# MCUPOWER.net
KiCad netlist of a schematic drawn in Altium Designer
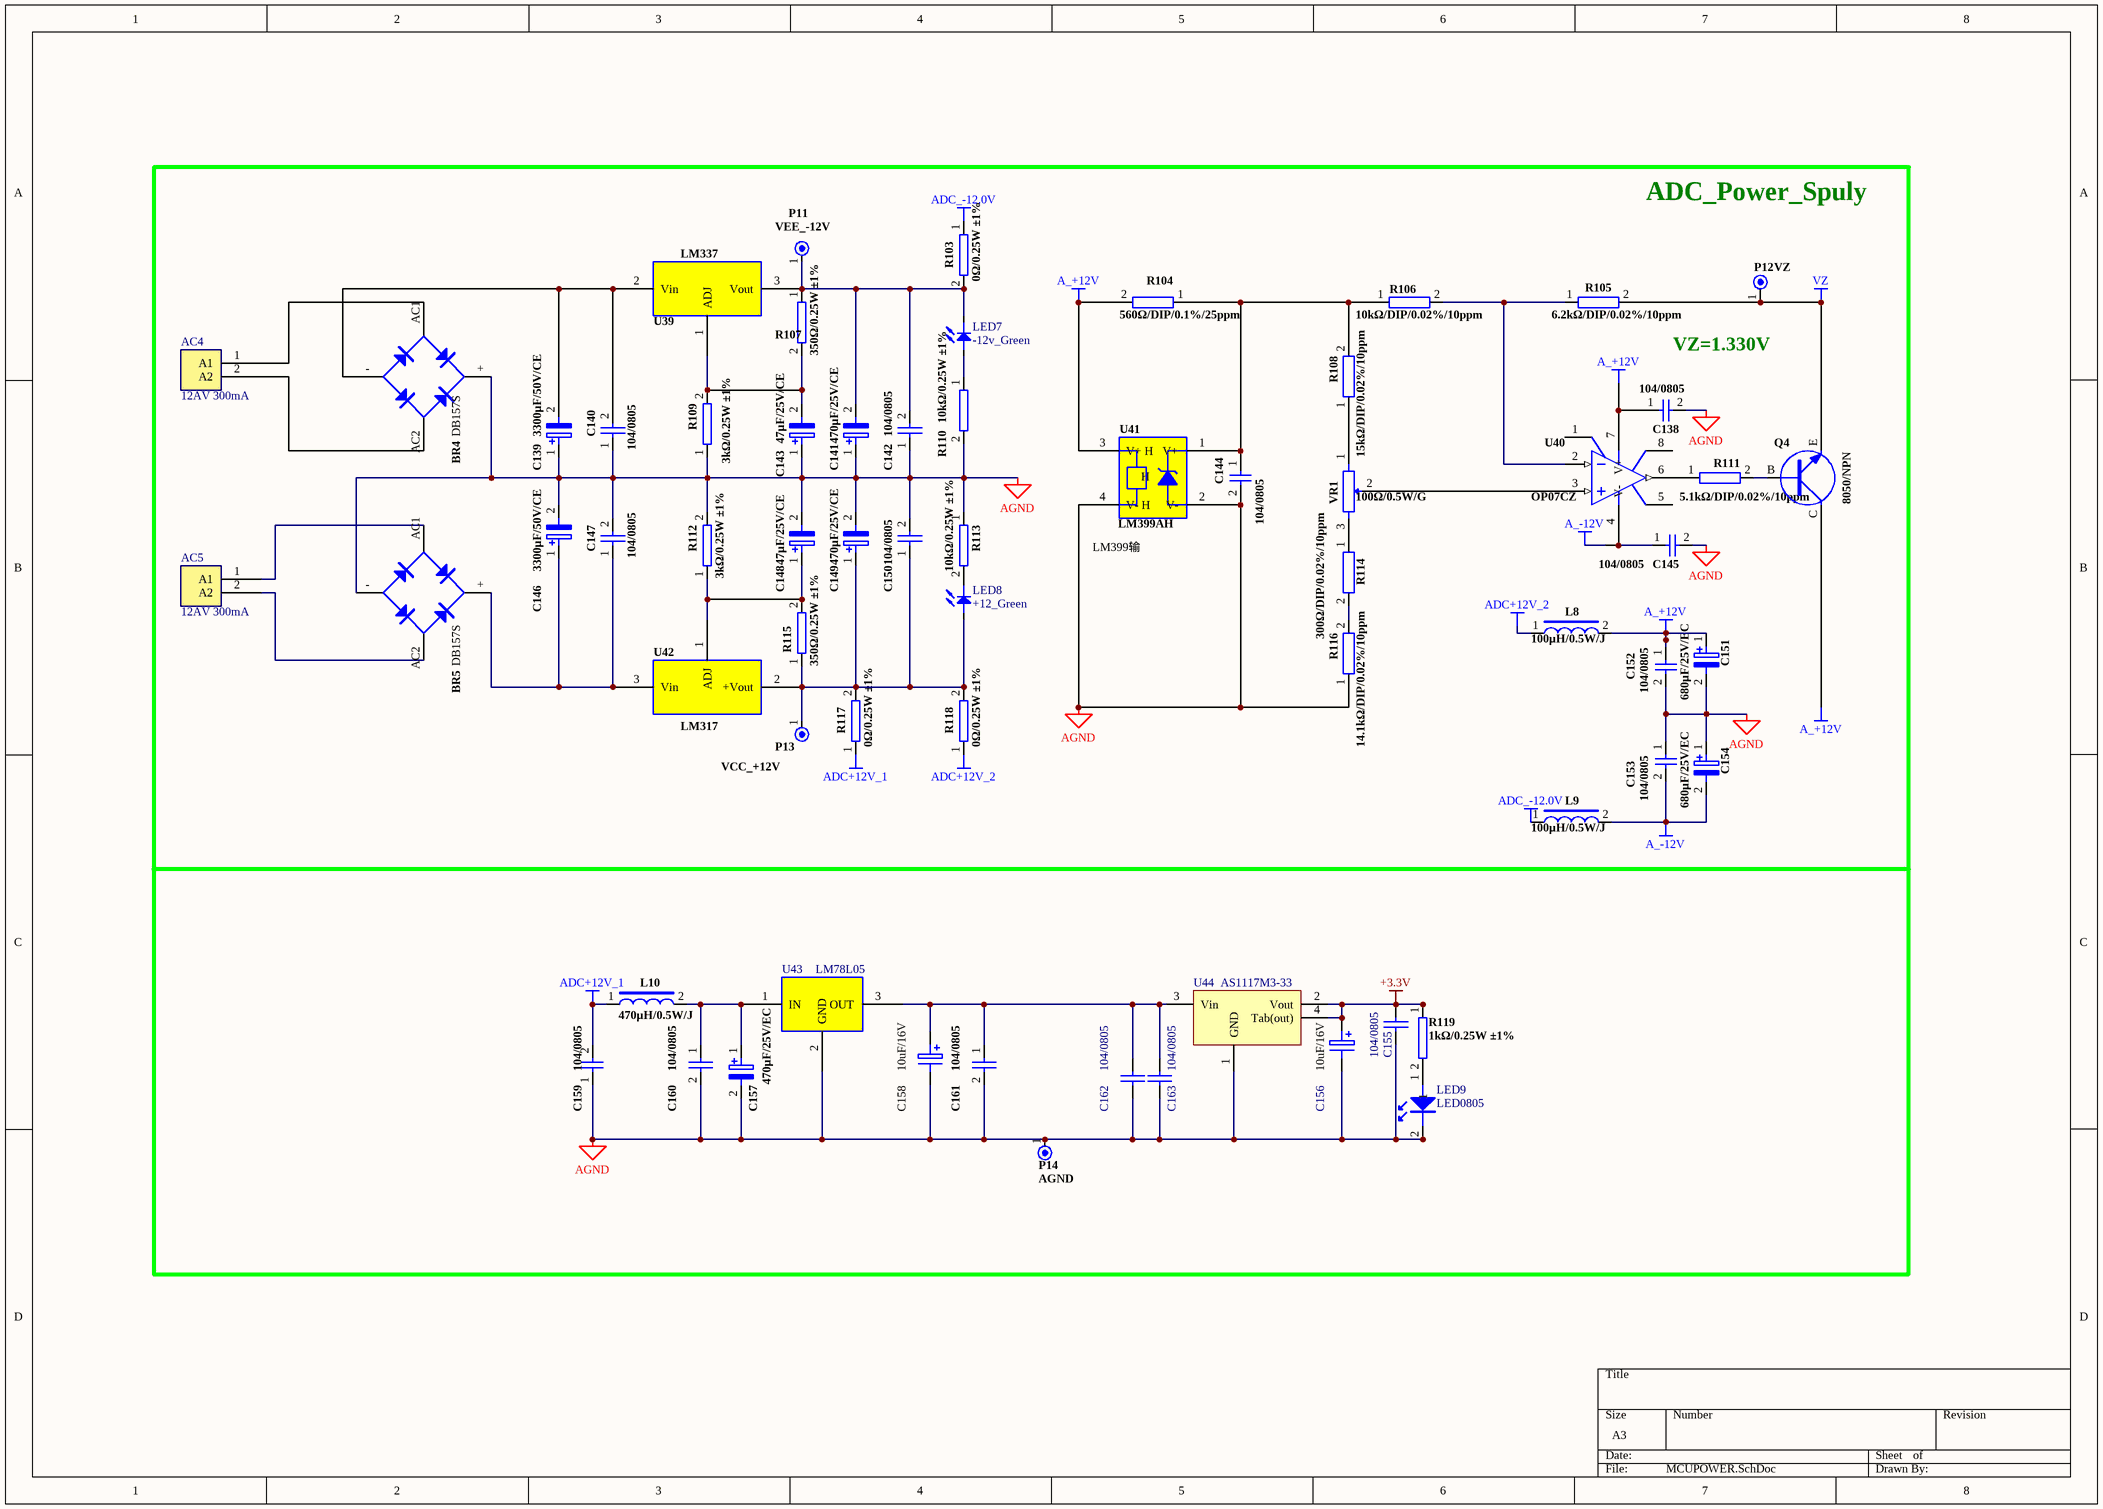
[diagram p0: MCUPOWER.SchDoc]

(export (version "E")
  (design (tool "Eeschema 10.0.6"))
  (components
    (comp (ref "AC4")
      (value "12AV 300mA")
      (footprint "HEADER2")
      (description "接线端子 AWG14-22 300VA 16A 5.0mm HEADER2")
      (libsource (lib "COOLCONTROL") (part "CON2"))
    )
    (comp (ref "AC5")
      (value "12AV 300mA")
      (footprint "HEADER2")
      (description "接线端子 AWG14-22 300VA 16A 5.0mm HEADER2")
      (libsource (lib "COOLCONTROL") (part "CON2"))
    )
    (comp (ref "BR4")
      (value "DB157S")
      (footprint "DB157S")
      (description "贴片整流桥 DB157S 50A/1000V")
      (libsource (lib "*") (part "NBRIDGE1"))
    )
    (comp (ref "BR5")
      (value "DB157S")
      (footprint "DB157S")
      (description "贴片整流桥 DB157S 50A/1000V")
      (libsource (lib "*") (part "NBRIDGE1"))
    )
    (comp (ref "C138")
      (value "104/0805")
      (footprint "C0805")
      (description "贴片电容 104/25V ±1% C0805")
      (libsource (lib "COOLCONTROL") (part "CAP"))
    )
    (comp (ref "C139")
      (value "3300μF/50V/CE")
      (footprint "RB.3/.6")
      (description "电解电容 3300μF/50V/CE ±10% RB.3/.6")
      (libsource (lib "*") (part "ELECTRO2"))
    )
    (comp (ref "C140")
      (value "104/0805")
      (footprint "C0805")
      (description "贴片电容 104/25V ±1% C0805")
      (libsource (lib "*") (part "CAP"))
    )
    (comp (ref "C141")
      (value "470μF/25V/CE")
      (footprint "RB.2/.4")
      (description "电解电容 470μF/25V/CE ±10% RB.2/.4")
      (libsource (lib "*") (part "ELECTRO2"))
    )
    (comp (ref "C142")
      (value "104/0805")
      (footprint "C0805")
      (description "贴片电容 104/25V ±1% C0805")
      (libsource (lib "*") (part "CAP"))
    )
    (comp (ref "C143")
      (value "47μF/25V/CE")
      (footprint "RB.1/.2")
      (description "电解电容 47μF/25V/CE ±10% RB.1/.2")
      (libsource (lib "*") (part "ELECTRO2"))
    )
    (comp (ref "C144")
      (value "104/0805")
      (footprint "C0805")
      (description "贴片电容 104/25V ±1% C0805")
      (libsource (lib "COOLCONTROL") (part "CAP"))
    )
    (comp (ref "C145")
      (value "104/0805")
      (footprint "C0805")
      (description "贴片电容 104/25V ±1% C0805")
      (libsource (lib "COOLCONTROL") (part "CAP"))
    )
    (comp (ref "C146")
      (value "3300μF/50V/CE")
      (footprint "RB.3/.6")
      (description "电解电容 3300μF/50V/CE ±10% RB.3/.6")
      (libsource (lib "*") (part "ELECTRO2"))
    )
    (comp (ref "C147")
      (value "104/0805")
      (footprint "C0805")
      (description "贴片电容 104/25V ±1% C0805")
      (libsource (lib "*") (part "CAP"))
    )
    (comp (ref "C148")
      (value "47μF/25V/CE")
      (footprint "RB.1/.2")
      (description "电解电容 47μF/25V/CE ±10% RB.1/.2")
      (libsource (lib "*") (part "ELECTRO2"))
    )
    (comp (ref "C149")
      (value "470μF/25V/CE")
      (footprint "RB.2/.4")
      (description "电解电容 470μF/25V/CE ±10% RB.2/.4")
      (libsource (lib "*") (part "ELECTRO2"))
    )
    (comp (ref "C150")
      (value "104/0805")
      (footprint "C0805")
      (description "贴片电容 104/25V ±1% C0805")
      (libsource (lib "*") (part "CAP"))
    )
    (comp (ref "C151")
      (value "680μF/25V/EC")
      (footprint "RB.2/.4")
      (description "电解电容 680μF/25V/EC ±10% RB.2/.4")
      (libsource (lib "COOLCONTROL") (part "ELECTRO2"))
    )
    (comp (ref "C152")
      (value "104/0805")
      (footprint "C0805")
      (description "贴片电容 104/25V ±1% C0805")
      (libsource (lib "COOLCONTROL") (part "CAP"))
    )
    (comp (ref "C153")
      (value "104/0805")
      (footprint "C0805")
      (description "贴片电容 104/25V ±1% C0805")
      (libsource (lib "COOLCONTROL") (part "CAP"))
    )
    (comp (ref "C154")
      (value "680μF/25V/EC")
      (footprint "RB.2/.4")
      (description "电解电容 680μF/25V/EC ±10% RB.2/.4")
      (libsource (lib "COOLCONTROL") (part "ELECTRO2"))
    )
    (comp (ref "C155")
      (value "104/0805")
      (footprint "C0805")
      (description "贴片电容 104/25V ±1% C0805")
      (libsource (lib "") (part "CAP_1"))
    )
    (comp (ref "C156")
      (value "10uF/16V")
      (footprint "C3216")
      (description "贴片钽电容 10uF/16V ±10% C3216")
      (libsource (lib "*") (part "ELECTRO1"))
    )
    (comp (ref "C157")
      (value "470μF/25V/EC")
      (footprint "RB.2/.4")
      (description "电解电容 470μF/25V/EC ±10% RB.2/.4")
      (libsource (lib "COOLCONTROL") (part "ELECTRO2"))
    )
    (comp (ref "C158")
      (value "10uF/16V")
      (footprint "C3216")
      (description "贴片钽电容 10uF/16V ±1% C3216")
      (libsource (lib "*") (part "ELECTRO1"))
    )
    (comp (ref "C159")
      (value "104/0805")
      (footprint "C0805")
      (description "贴片电容 104/25V ±1% C0805")
      (libsource (lib "") (part "CAP_2"))
    )
    (comp (ref "C160")
      (value "104/0805")
      (footprint "C0805")
      (description "贴片电容 104/25V ±1% C0805")
      (libsource (lib "*") (part "CAP"))
    )
    (comp (ref "C161")
      (value "104/0805")
      (footprint "C0805")
      (description "贴片电容 104/25V ±1% C0805")
      (libsource (lib "*") (part "CAP"))
    )
    (comp (ref "C162")
      (value "104/0805")
      (footprint "C0805")
      (description "贴片电容 104/25V ±1% C0805")
      (libsource (lib "") (part "CAP_1"))
    )
    (comp (ref "C163")
      (value "104/0805")
      (footprint "C0805")
      (description "贴片电容 104/25V ±1% C0805")
      (libsource (lib "") (part "CAP_1"))
    )
    (comp (ref "L8")
      (value "100μH/0.5W/J")
      (footprint "AXIAL0.4")
      (description "直插电感 100μH/0.5W ±5% AXIAL0.4")
      (libsource (lib "COOLCONTROL") (part "INDUCTOR2"))
    )
    (comp (ref "L9")
      (value "100μH/0.5W/J")
      (footprint "AXIAL0.4")
      (description "直插电感 100μH/0.5W ±5% AXIAL0.4")
      (libsource (lib "COOLCONTROL") (part "INDUCTOR2"))
    )
    (comp (ref "L10")
      (value "470μH/0.5W/J")
      (footprint "COOLCONTROL:AXIAL0.4")
      (description "直插电感 470μH/0.5W ±5% AXIAL0.4")
      (libsource (lib "COOLCONTROL") (part "INDUCTOR2"))
    )
    (comp (ref "LED7")
      (value "-12v_Green")
      (footprint "LED_0805")
      (description "贴片LED灯 绿色 2.0V 20mA LED_0805")
      (libsource (lib "COOLCONTROL") (part "B_LED"))
    )
    (comp (ref "LED8")
      (value "+12_Green")
      (footprint "LED_0805")
      (description "贴片LED灯 绿色 2.0V 20mA LED_0805")
      (libsource (lib "MasterBoard_Prj") (part "B_LED"))
    )
    (comp (ref "LED9")
      (value "LED0805")
      (footprint "LED_0805")
      (description "贴片LED灯 蓝色 2.0V 20mA LED_0805")
      (libsource (lib "COOLCONTROL") (part "LED0805"))
    )
    (comp (ref "P11")
      (value "VEE_-12V")
      (footprint "TESTSMD")
      (description "测试点")
      (libsource (lib "*") (part "CON1"))
    )
    (comp (ref "P12")
      (value "VZ")
      (footprint "COOLCONTROL:TESTSMD")
      (description "测试点")
      (libsource (lib "COOLCONTROL") (part "CON1"))
    )
    (comp (ref "P13")
      (value "VCC_+12V")
      (footprint "TESTSMD")
      (description "测试点")
      (libsource (lib "*") (part "CON1"))
    )
    (comp (ref "P14")
      (value "AGND")
      (footprint "TESTSMD")
      (description "测试点")
      (libsource (lib "*") (part "CON1"))
    )
    (comp (ref "Q4")
      (value "8050/NPN")
      (footprint "TO92A")
      (description "三极管 8050/NPN TO92A")
      (libsource (lib "COOLCONTROL") (part "NPN"))
    )
    (comp (ref "R103")
      (value "0Ω/0.25W ±1%")
      (footprint "R0805")
      (description "贴片电阻 0Ω 0.25W ±1% R0805")
      (libsource (lib "*") (part "RES2"))
    )
    (comp (ref "R104")
      (value "560Ω/DIP/0.1%/25ppm")
      (footprint "AXIAL-0.6-R")
      (description "高精度电阻 560Ω DIP 1W ±0.1% 25ppm AXIAL-0.6-R")
      (libsource (lib "COOLCONTROL") (part "RES2"))
    )
    (comp (ref "R105")
      (value "6.2kΩ/DIP/0.02%/10ppm")
      (footprint "AXIAL-0.6-R")
      (description "高精度电阻 6.2kΩ DIP 1W ±0.02% 10ppm AXIAL-0.6-R")
      (libsource (lib "") (part "RES3_1"))
    )
    (comp (ref "R106")
      (value "10kΩ/DIP/0.02%/10ppm")
      (footprint "AXIAL-0.6-R")
      (description "高精度电阻 10kΩ DIP 1W ±0.02% 10ppm AXIAL-0.6-R")
      (libsource (lib "") (part "RES3_1"))
    )
    (comp (ref "R107")
      (value "350Ω/0.25W ±1%")
      (footprint "R0805")
      (description "贴片电阻 350Ω 0.25W ±1% R0805")
      (libsource (lib "*") (part "RES2"))
    )
    (comp (ref "R108")
      (value "15kΩ/DIP/0.02%/10ppm")
      (footprint "AXIAL-0.6-R")
      (description "高精度电阻 15kΩ DIP 1W ±0.02% 10ppm AXIAL-0.6-R")
      (libsource (lib "COOLCONTROL") (part "RES3"))
    )
    (comp (ref "R109")
      (value "3kΩ/0.25W ±1%")
      (footprint "R0805")
      (description "贴片电阻 3kΩ 0.25W ±1% R0805")
      (libsource (lib "*") (part "RES2"))
    )
    (comp (ref "R110")
      (value "10kΩ/0.25W ±1%")
      (footprint "R0805")
      (description "贴片电阻 10kΩ 0.25W ±1% R0805")
      (libsource (lib "*") (part "RES2"))
    )
    (comp (ref "R111")
      (value "5.1kΩ/DIP/0.02%/10ppm")
      (footprint "AXIAL-0.6-R")
      (description "高精度电阻 5.1kΩ DIP 1W ±0.02% 10ppm AXIAL-0.6-R")
      (libsource (lib "") (part "RES2_1"))
    )
    (comp (ref "R112")
      (value "3kΩ/0.25W ±1%")
      (footprint "R0805")
      (description "贴片电阻 3kΩ 0.25W ±1% R0805")
      (libsource (lib "*") (part "RES2"))
    )
    (comp (ref "R113")
      (value "10kΩ/0.25W ±1%")
      (footprint "R0805")
      (description "贴片电阻 10kΩ 0.25W ±1% R0805")
      (libsource (lib "*") (part "RES2"))
    )
    (comp (ref "R114")
      (value "300Ω/DIP/0.02%/10ppm")
      (footprint "AXIAL-0.6-R")
      (description "高精度电阻 300Ω DIP 1W ±0.02% 10ppm AXIAL-0.6-R")
      (libsource (lib "") (part "RES2_2"))
    )
    (comp (ref "R115")
      (value "350Ω/0.25W ±1%")
      (footprint "R0805")
      (description "贴片电阻 350Ω 0.25W ±1% R0805")
      (libsource (lib "*") (part "RES2"))
    )
    (comp (ref "R116")
      (value "14.1kΩ/DIP/0.02%/10ppm")
      (footprint "AXIAL-0.6-R")
      (description "高精度电阻 14.1kΩ DIP 1W ±0.02% 10ppm AXIAL-0.6-R")
      (libsource (lib "COOLCONTROL") (part "RES3"))
    )
    (comp (ref "R117")
      (value "0Ω/0.25W ±1%")
      (footprint "R0805")
      (description "贴片电阻 0Ω 0.25W ±1% R0805")
      (libsource (lib "*") (part "RES2"))
    )
    (comp (ref "R118")
      (value "0Ω/0.25W ±1%")
      (footprint "R0805")
      (description "贴片电阻 0Ω 0.25W ±1% R0805")
      (libsource (lib "*") (part "RES2"))
    )
    (comp (ref "R119")
      (value "1kΩ/0.25W ±1%")
      (footprint "R0805")
      (description "贴片电阻 1kΩ 0.25W ±1% R0805")
      (libsource (lib "*") (part "RES2"))
    )
    (comp (ref "U39")
      (value "LM337")
      (footprint "TO220H")
      (description "线性可调稳压IC LM337 TO220H")
      (libsource (lib "*") (part "LM337"))
    )
    (comp (ref "U40")
      (value "OP07CZ")
      (footprint "SO-8")
      (description "运算放大器 OP07CZ SO-8")
      (libsource (lib "COOLCONTROL") (part "OP07CZ"))
    )
    (comp (ref "U41")
      (value "LM399AH")
      (footprint "LM399")
      (description "高精度电压比较器 LM399AH TO46-4")
      (libsource (lib "COOLCONTROL") (part "LM399AH"))
    )
    (comp (ref "U42")
      (value "LM317")
      (footprint "TO220H")
      (description "线性可调稳压IC LM317 TO220H")
      (libsource (lib "*") (part "LM317"))
    )
    (comp (ref "U43")
      (value "LM78L05")
      (footprint "TO-220")
      (description "线性稳压芯片 LM78L05 TO-220")
      (libsource (lib "COOLCONTROL") (part "LM78L05"))
    )
    (comp (ref "U44")
      (value "AS1117M3-33")
      (footprint "SOT-223-3L(M3)")
      (description "线性稳压管 AS1117M3-33 SOT-223")
      (libsource (lib "COOLCONTROL") (part "AS1117M3-33"))
    )
    (comp (ref "VR1")
      (value "100Ω/0.5W/G")
      (footprint "3224W")
      (description "高精密可调电位器 100Ω 0.5W/G 3224W")
      (libsource (lib "COOLCONTROL") (part "RPOT"))
    )
  )
  (nets
    (net (code "1") (name "+3.3V") (class "Default")
      (node (ref "C155") (pin "1") (pinfunction "1_1") (pintype "passive"))
      (node (ref "C156") (pin "1") (pinfunction "1_1") (pintype "passive"))
      (node (ref "R119") (pin "1") (pintype "passive"))
      (node (ref "U44") (pin "2") (pinfunction "Vout_2") (pintype "passive"))
      (node (ref "U44") (pin "4") (pinfunction "Tab(out)_4") (pintype "passive"))
    )
    (net (code "2") (name "ADC+12V_1") (class "Default")
      (node (ref "C159") (pin "2") (pintype "passive"))
      (node (ref "L10") (pin "1") (pintype "passive"))
      (node (ref "R117") (pin "1") (pintype "passive"))
    )
    (net (code "3") (name "ADC+12V_2") (class "Default")
      (node (ref "L8") (pin "1") (pintype "passive"))
      (node (ref "R118") (pin "1") (pintype "passive"))
    )
    (net (code "4") (name "ADC_-12.0V") (class "Default")
      (node (ref "L9") (pin "1") (pintype "passive"))
      (node (ref "R103") (pin "1") (pintype "passive"))
    )
    (net (code "5") (name "AGND") (class "Default")
      (node (ref "BR4") (pin "+") (pinfunction "V+_+") (pintype "passive"))
      (node (ref "BR5") (pin "-") (pinfunction "V-_-") (pintype "passive"))
      (node (ref "C138") (pin "2") (pintype "passive"))
      (node (ref "C139") (pin "1") (pintype "passive"))
      (node (ref "C140") (pin "1") (pintype "passive"))
      (node (ref "C141") (pin "1") (pintype "passive"))
      (node (ref "C142") (pin "1") (pintype "passive"))
      (node (ref "C143") (pin "1") (pintype "passive"))
      (node (ref "C144") (pin "2") (pintype "passive"))
      (node (ref "C145") (pin "2") (pintype "passive"))
      (node (ref "C146") (pin "2") (pintype "passive"))
      (node (ref "C147") (pin "2") (pintype "passive"))
      (node (ref "C148") (pin "2") (pintype "passive"))
      (node (ref "C149") (pin "2") (pintype "passive"))
      (node (ref "C150") (pin "2") (pintype "passive"))
      (node (ref "C151") (pin "2") (pintype "passive"))
      (node (ref "C152") (pin "2") (pintype "passive"))
      (node (ref "C153") (pin "1") (pintype "passive"))
      (node (ref "C154") (pin "1") (pintype "passive"))
      (node (ref "C155") (pin "2") (pinfunction "2_2") (pintype "passive"))
      (node (ref "C156") (pin "2") (pinfunction "2_2") (pintype "passive"))
      (node (ref "C157") (pin "2") (pintype "passive"))
      (node (ref "C158") (pin "2") (pinfunction "2_2") (pintype "passive"))
      (node (ref "C159") (pin "1") (pintype "passive"))
      (node (ref "C160") (pin "2") (pintype "passive"))
      (node (ref "C161") (pin "2") (pintype "passive"))
      (node (ref "C162") (pin "2") (pinfunction "2_2") (pintype "passive"))
      (node (ref "C163") (pin "2") (pinfunction "2_2") (pintype "passive"))
      (node (ref "LED9") (pin "2") (pinfunction "2_2") (pintype "passive"))
      (node (ref "P14") (pin "1") (pintype "passive"))
      (node (ref "R109") (pin "1") (pintype "passive"))
      (node (ref "R110") (pin "2") (pintype "passive"))
      (node (ref "R112") (pin "2") (pintype "passive"))
      (node (ref "R113") (pin "1") (pintype "passive"))
      (node (ref "R116") (pin "1") (pintype "passive"))
      (node (ref "U41") (pin "2") (pinfunction "V-_2") (pintype "power_in"))
      (node (ref "U41") (pin "4") (pinfunction "V-_H_4") (pintype "power_in"))
      (node (ref "U43") (pin "2") (pinfunction "GND_2") (pintype "passive"))
      (node (ref "U44") (pin "1") (pinfunction "GND_1") (pintype "passive"))
    )
    (net (code "6") (name "A_+12V") (class "Default")
      (node (ref "C138") (pin "1") (pintype "passive"))
      (node (ref "C151") (pin "1") (pintype "passive"))
      (node (ref "C152") (pin "1") (pintype "passive"))
      (node (ref "L8") (pin "2") (pintype "passive"))
      (node (ref "Q4") (pin "C") (pintype "passive"))
      (node (ref "R104") (pin "2") (pintype "passive"))
      (node (ref "U40") (pin "7") (pinfunction "V+_7") (pintype "power_in"))
      (node (ref "U41") (pin "3") (pinfunction "V+_H_3") (pintype "power_in"))
    )
    (net (code "7") (name "A_-12V") (class "Default")
      (node (ref "C145") (pin "1") (pintype "passive"))
      (node (ref "C153") (pin "2") (pintype "passive"))
      (node (ref "C154") (pin "2") (pintype "passive"))
      (node (ref "L9") (pin "2") (pintype "passive"))
      (node (ref "U40") (pin "4") (pinfunction "V-_4") (pintype "power_in"))
    )
    (net (code "8") (name "Net-(AC4-A1)") (class "Default")
      (node (ref "AC4") (pin "1") (pinfunction "A1_1") (pintype "passive"))
      (node (ref "BR4") (pin "AC1") (pinfunction "AC1_AC1") (pintype "passive"))
    )
    (net (code "9") (name "Net-(AC4-A2)") (class "Default")
      (node (ref "AC4") (pin "2") (pinfunction "A2_2") (pintype "passive"))
      (node (ref "BR4") (pin "AC2") (pinfunction "AC2_AC2") (pintype "passive"))
    )
    (net (code "10") (name "Net-(AC5-A1)") (class "Default")
      (node (ref "AC5") (pin "1") (pinfunction "A1_1") (pintype "passive"))
      (node (ref "BR5") (pin "AC1") (pinfunction "AC1_AC1") (pintype "passive"))
    )
    (net (code "11") (name "Net-(AC5-A2)") (class "Default")
      (node (ref "AC5") (pin "2") (pinfunction "A2_2") (pintype "passive"))
      (node (ref "BR5") (pin "AC2") (pinfunction "AC2_AC2") (pintype "passive"))
    )
    (net (code "12") (name "Net-(BR4-V-)") (class "Default")
      (node (ref "BR4") (pin "-") (pinfunction "V-_-") (pintype "passive"))
      (node (ref "C139") (pin "2") (pintype "passive"))
      (node (ref "C140") (pin "2") (pintype "passive"))
      (node (ref "U39") (pin "2") (pinfunction "Vin_2") (pintype "passive"))
    )
    (net (code "13") (name "Net-(BR5-V+)") (class "Default")
      (node (ref "BR5") (pin "+") (pinfunction "V+_+") (pintype "passive"))
      (node (ref "C146") (pin "1") (pintype "passive"))
      (node (ref "C147") (pin "1") (pintype "passive"))
      (node (ref "U42") (pin "3") (pinfunction "Vin_3") (pintype "passive"))
    )
    (net (code "14") (name "Net-(LED7-Pad1)") (class "Default")
      (node (ref "LED7") (pin "1") (pinfunction "1_1") (pintype "passive"))
      (node (ref "R110") (pin "1") (pintype "passive"))
    )
    (net (code "15") (name "Net-(LED8-Pad2)") (class "Default")
      (node (ref "LED8") (pin "2") (pinfunction "2_2") (pintype "passive"))
      (node (ref "R113") (pin "2") (pintype "passive"))
    )
    (net (code "16") (name "Net-(LED9-Pad1)") (class "Default")
      (node (ref "LED9") (pin "1") (pinfunction "1_1") (pintype "passive"))
      (node (ref "R119") (pin "2") (pintype "passive"))
    )
    (net (code "17") (name "Net-(Q4-PadB)") (class "Default")
      (node (ref "Q4") (pin "B") (pintype "passive"))
      (node (ref "R111") (pin "2") (pintype "passive"))
    )
    (net (code "18") (name "Net-(R105-Pad1)") (class "Default")
      (node (ref "R105") (pin "1") (pintype "passive"))
      (node (ref "R106") (pin "2") (pintype "passive"))
      (node (ref "U40") (pin "2") (pintype "input"))
    )
    (net (code "19") (name "Net-(R108-Pad1)") (class "Default")
      (node (ref "R108") (pin "1") (pintype "passive"))
      (node (ref "VR1") (pin "1") (pintype "passive"))
    )
    (net (code "20") (name "Net-(R111-Pad1)") (class "Default")
      (node (ref "R111") (pin "1") (pintype "passive"))
      (node (ref "U40") (pin "6") (pintype "output"))
    )
    (net (code "21") (name "Net-(R114-Pad1)") (class "Default")
      (node (ref "R114") (pin "1") (pintype "passive"))
      (node (ref "VR1") (pin "3") (pintype "passive"))
    )
    (net (code "22") (name "Net-(R114-Pad2)") (class "Default")
      (node (ref "R114") (pin "2") (pintype "passive"))
      (node (ref "R116") (pin "2") (pintype "passive"))
    )
    (net (code "23") (name "Net-(U39-ADJ)") (class "Default")
      (node (ref "C143") (pin "2") (pintype "passive"))
      (node (ref "R107") (pin "2") (pintype "passive"))
      (node (ref "R109") (pin "2") (pintype "passive"))
      (node (ref "U39") (pin "1") (pinfunction "ADJ_1") (pintype "passive"))
    )
    (net (code "24") (name "Net-(U39-Vout)") (class "Default")
      (node (ref "C141") (pin "2") (pintype "passive"))
      (node (ref "C142") (pin "2") (pintype "passive"))
      (node (ref "LED7") (pin "2") (pinfunction "2_2") (pintype "passive"))
      (node (ref "P11") (pin "1") (pintype "passive"))
      (node (ref "R103") (pin "2") (pintype "passive"))
      (node (ref "R107") (pin "1") (pintype "passive"))
      (node (ref "U39") (pin "3") (pinfunction "Vout_3") (pintype "passive"))
    )
    (net (code "25") (name "Net-(U40-Pad3)") (class "Default")
      (node (ref "U40") (pin "3") (pintype "input"))
      (node (ref "VR1") (pin "2") (pintype "passive"))
    )
    (net (code "26") (name "Net-(U41-V+)") (class "Default")
      (node (ref "C144") (pin "1") (pintype "passive"))
      (node (ref "R104") (pin "1") (pintype "passive"))
      (node (ref "R106") (pin "1") (pintype "passive"))
      (node (ref "R108") (pin "2") (pintype "passive"))
      (node (ref "U41") (pin "1") (pinfunction "V+_1") (pintype "power_in"))
    )
    (net (code "27") (name "Net-(U42-+Vout)") (class "Default")
      (node (ref "C149") (pin "1") (pintype "passive"))
      (node (ref "C150") (pin "1") (pintype "passive"))
      (node (ref "LED8") (pin "1") (pinfunction "1_1") (pintype "passive"))
      (node (ref "P13") (pin "1") (pintype "passive"))
      (node (ref "R115") (pin "1") (pintype "passive"))
      (node (ref "R117") (pin "2") (pintype "passive"))
      (node (ref "R118") (pin "2") (pintype "passive"))
      (node (ref "U42") (pin "2") (pinfunction "+Vout_2") (pintype "passive"))
    )
    (net (code "28") (name "Net-(U42-ADJ)") (class "Default")
      (node (ref "C148") (pin "1") (pintype "passive"))
      (node (ref "R112") (pin "1") (pintype "passive"))
      (node (ref "R115") (pin "2") (pintype "passive"))
      (node (ref "U42") (pin "1") (pinfunction "ADJ_1") (pintype "passive"))
    )
    (net (code "29") (name "Net-(U43-IN)") (class "Default")
      (node (ref "C157") (pin "1") (pintype "passive"))
      (node (ref "C160") (pin "1") (pintype "passive"))
      (node (ref "L10") (pin "2") (pintype "passive"))
      (node (ref "U43") (pin "1") (pinfunction "IN_1") (pintype "passive"))
    )
    (net (code "30") (name "Net-(U43-OUT)") (class "Default")
      (node (ref "C158") (pin "1") (pinfunction "1_1") (pintype "passive"))
      (node (ref "C161") (pin "1") (pintype "passive"))
      (node (ref "C162") (pin "1") (pinfunction "1_1") (pintype "passive"))
      (node (ref "C163") (pin "1") (pinfunction "1_1") (pintype "passive"))
      (node (ref "U43") (pin "3") (pinfunction "OUT_3") (pintype "passive"))
      (node (ref "U44") (pin "3") (pinfunction "Vin_3") (pintype "passive"))
    )
    (net (code "31") (name "VZ") (class "Default")
      (node (ref "P12") (pin "1") (pintype "passive"))
      (node (ref "Q4") (pin "E") (pintype "passive"))
      (node (ref "R105") (pin "2") (pintype "passive"))
    )
    (net (code "32") (name "unconnected-(U40-Pad1)") (class "Default")
      (node (ref "U40") (pin "1") (pintype "passive"))
    )
    (net (code "33") (name "unconnected-(U40-Pad5)") (class "Default")
      (node (ref "U40") (pin "5") (pintype "passive"))
    )
    (net (code "34") (name "unconnected-(U40-Pad8)") (class "Default")
      (node (ref "U40") (pin "8") (pintype "passive"))
    )
  )
)
